# JL7016M8.net
KiCad netlist of a schematic drawn in Altium Designer
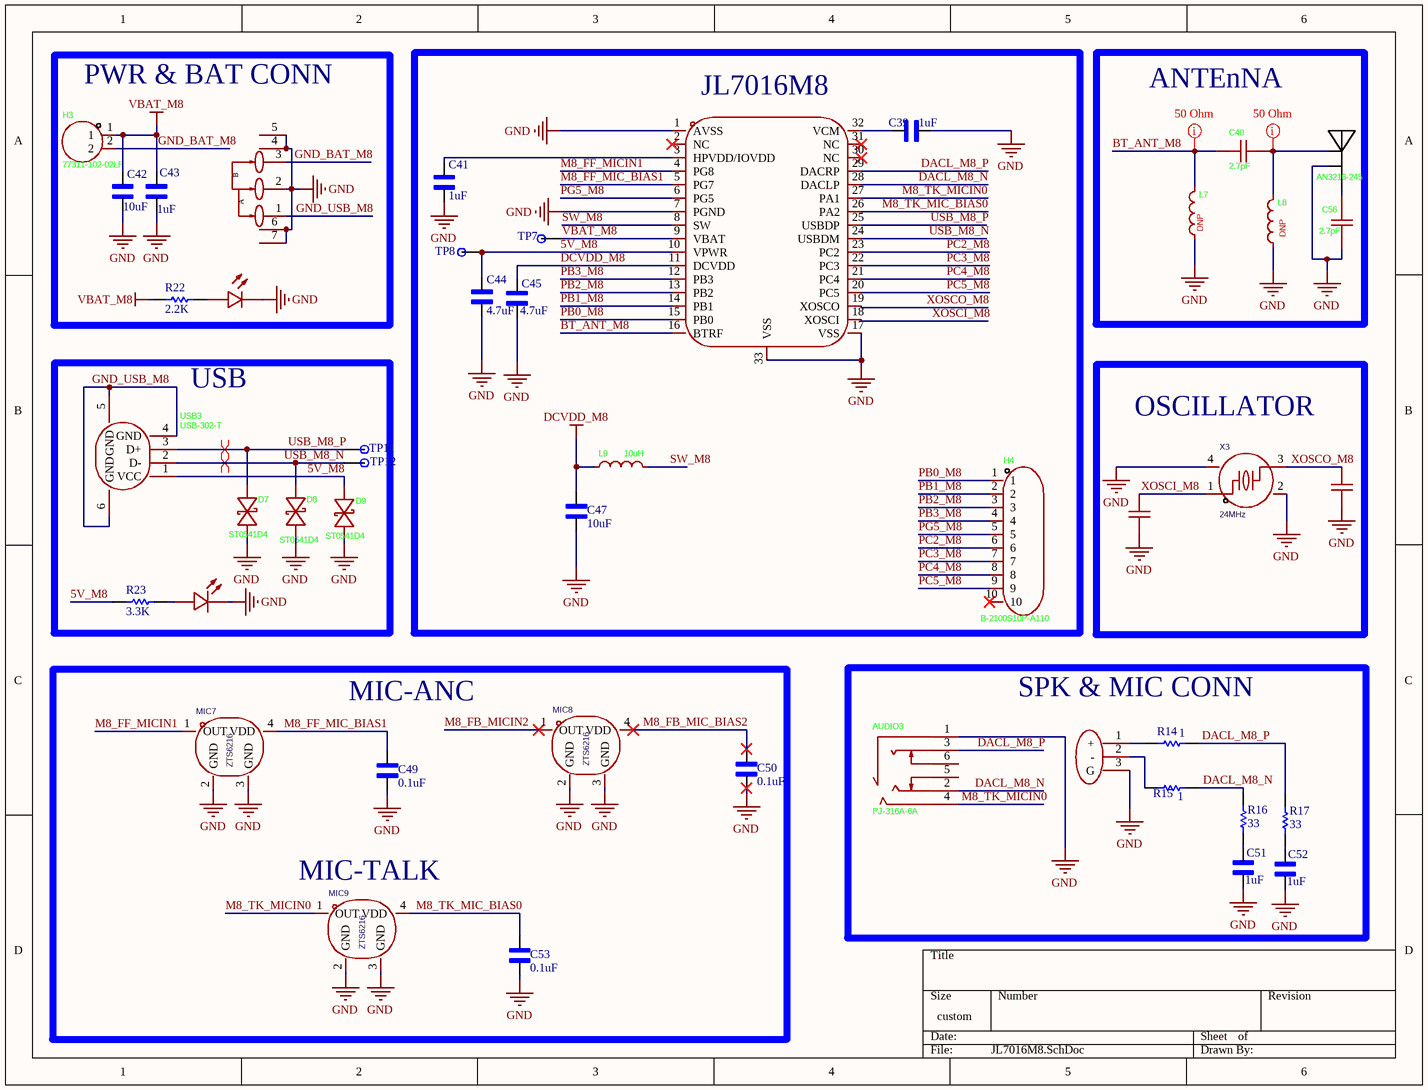
[diagram p0: JL7016M8.SchDoc]

(export (version "E")
  (design (tool "Eeschema 10.0.6"))
  (components
    (comp (ref "ANT3")
      (value "AN3216-245")
      (footprint "CUSTOME ANTEENA")
      (fields (field (name "MANUFACTURER") "Rainsun(霖昱微)") (field (name "POWER") "1W"))
      (libsource (lib "JEILI_DEV_BOARD") (part "AN3216-245"))
    )
    (comp (ref "AUDIO3")
      (value "PJ-316A-6A")
      (footprint "AUDIO-SMD_PJ-316A-6A")
      (fields (field (name "MANUFACTURER") "韩国韩荣"))
      (libsource (lib "JEILI_DEV_BOARD") (part "PJ-316A-6A"))
    )
    (comp (ref "C39") (value "1uF") (footprint "CAPC3216X170N") (libsource (lib "") (part "CAP_1uF_2")))
    (comp (ref "C40")
      (value "2.7pF")
      (footprint "C0603")
      (fields (field (name "MANUFACTURER") "FH(风华)") (field (name "MANUFACTURER PART") "0603CG2R7C500NT"))
      (libsource (lib "JEILI_DEV_BOARD") (part "0603CG2R7C500NT"))
    )
    (comp (ref "C41")
      (value "1uF")
      (footprint "CAPC3216X170N")
      (libsource (lib "JEILI_DEV_BOARD") (part "CAP_1uF"))
    )
    (comp (ref "C42")
      (value "10uF")
      (footprint "CAPC3216X170N")
      (libsource (lib "JEILI_DEV_BOARD") (part "CAP_10F"))
    )
    (comp (ref "C43")
      (value "1uF")
      (footprint "CAPC3216X170N")
      (libsource (lib "JEILI_DEV_BOARD") (part "CAP_1uF"))
    )
    (comp (ref "C44")
      (value "4.7uF")
      (footprint "CAPC3216X170N")
      (fields (field (name "Comment") "1uF"))
      (libsource (lib "JEILI_DEV_BOARD") (part "CAP_1uF"))
    )
    (comp (ref "C45")
      (value "4.7uF")
      (footprint "CAPC3216X170N")
      (fields (field (name "Comment") "1uF"))
      (libsource (lib "JEILI_DEV_BOARD") (part "CAP_1uF"))
    )
    (comp (ref "C46")
      (value "12pF")
      (footprint "CAPC3216X170N")
      (fields
        (field (name "MANUFACTURER") "FH(风华)")
        (field (name "MANUFACTURER PART") "0402CG120J500NT")
        (field (name "TOLERANCE") "±5%")
      )
      (libsource (lib "JEILI_DEV_BOARD") (part "0402CG120J500NT"))
    )
    (comp (ref "C47")
      (value "10uF")
      (footprint "CAPC3216X170N")
      (libsource (lib "JEILI_DEV_BOARD") (part "CAP_10F"))
    )
    (comp (ref "C48")
      (value "12pF")
      (footprint "CAPC3216X170N")
      (fields
        (field (name "MANUFACTURER") "FH(风华)")
        (field (name "MANUFACTURER PART") "0402CG120J500NT")
        (field (name "TOLERANCE") "±5%")
      )
      (libsource (lib "JEILI_DEV_BOARD") (part "0402CG120J500NT"))
    )
    (comp (ref "C49")
      (value "0.1uF")
      (footprint "CAPC3216X170N")
      (description "100nF 10V X7R ±5% 0402 Multilayer Ceramic Capacitors MLCC - SMD/SMT ROHS")
      (fields (field (name "MANUFACTURER") "Walsin Tech Corp") (field (name "MFR.PART #") "0402B104J100CT"))
      (libsource (lib "Glasses_EEG_V2.0") (part "CAP_0.1uF"))
    )
    (comp (ref "C50")
      (value "0.1uF")
      (footprint "CAPC3216X170N")
      (description "100nF 10V X7R ±5% 0402 Multilayer Ceramic Capacitors MLCC - SMD/SMT ROHS")
      (fields (field (name "MANUFACTURER") "Walsin Tech Corp") (field (name "MFR.PART #") "0402B104J100CT"))
      (libsource (lib "Glasses_EEG_V2.0") (part "CAP_0.1uF"))
    )
    (comp (ref "C51") (value "1uF") (footprint "CAPC3216X170N") (libsource (lib "") (part "CAP_1uF_1")))
    (comp (ref "C52") (value "1uF") (footprint "CAPC3216X170N") (libsource (lib "") (part "CAP_1uF_1")))
    (comp (ref "C53")
      (value "0.1uF")
      (footprint "CAPC3216X170N")
      (description "100nF 10V X7R ±5% 0402 Multilayer Ceramic Capacitors MLCC - SMD/SMT ROHS")
      (fields (field (name "MANUFACTURER") "Walsin Tech Corp") (field (name "MFR.PART #") "0402B104J100CT"))
      (libsource (lib "Glasses_EEG_V2.0") (part "CAP_0.1uF"))
    )
    (comp (ref "C56")
      (value "2.7pF")
      (footprint "C0402")
      (fields (field (name "MANUFACTURER") "FH(风华)") (field (name "MANUFACTURER PART") "0603CG2R7C500NT"))
      (libsource (lib "JEILI_DEV_BOARD") (part "0603CG2R7C500NT"))
    )
    (comp (ref "D7")
      (value "ST0541D4")
      (footprint "DFN1006-BI")
      (fields (field (name "MANUFACTURER") "Leiditech(雷卯电子)"))
      (libsource (lib "JEILI_DEV_BOARD") (part "ST0541D4"))
    )
    (comp (ref "D8")
      (value "ST0541D4")
      (footprint "DFN1006-BI")
      (fields (field (name "MANUFACTURER") "Leiditech(雷卯电子)"))
      (libsource (lib "JEILI_DEV_BOARD") (part "ST0541D4"))
    )
    (comp (ref "D9")
      (value "ST0541D4")
      (footprint "DFN1006-BI")
      (fields (field (name "MANUFACTURER") "Leiditech(雷卯电子)"))
      (libsource (lib "JEILI_DEV_BOARD") (part "ST0541D4"))
    )
    (comp (ref "H3")
      (value "77311-102-02LF")
      (footprint "HDR-TH_2P-P2.54-V-M-1")
      (fields (field (name "MANUFACTURER") "Amphenol"))
      (libsource (lib "JEILI_DEV_BOARD") (part "77311-102-02LF"))
    )
    (comp (ref "H4")
      (value "B-2100S10P-A110")
      (footprint "HDR-TH_10P-P2.54-V-M-1")
      (fields (field (name "MANUFACTURER") "Ckmtw(灿科盟)"))
      (libsource (lib "JEILI_DEV_BOARD") (part "B-2100S10P-A110"))
    )
    (comp (ref "L7")
      (value "DNP")
      (footprint "L0603")
      (fields
        (field (name "MANUFACTURER") "muRata(村田)")
        (field (name "MANUFACTURER PART") "DFE18SAN1R0ME0L")
        (field (name "TOLERANCE") "±20%")
      )
      (libsource (lib "JEILI_DEV_BOARD") (part "33nH"))
    )
    (comp (ref "L8")
      (value "DNP")
      (footprint "L0603")
      (fields
        (field (name "MANUFACTURER") "muRata(村田)")
        (field (name "MANUFACTURER PART") "DFE18SAN1R0ME0L")
        (field (name "TOLERANCE") "±20%")
      )
      (libsource (lib "JEILI_DEV_BOARD") (part "33nH"))
    )
    (comp (ref "L9") (value "10uH") (footprint "L0603") (libsource (lib "JEILI_DEV_BOARD") (part "10uH")))
    (comp (ref "LED5")
      (value "LTST-C191GKT")
      (footprint "LED0603-R-RD_GREEN")
      (fields (field (name "MANUFACTURER") "LITEON(光宝)"))
      (libsource (lib "JEILI_DEV_BOARD") (part "LTST-C191GKT"))
    )
    (comp (ref "LED6")
      (value "KT-0603R")
      (footprint "LED0603-RD")
      (fields (field (name "MANUFACTURER") "KENTO"))
      (libsource (lib "JEILI_DEV_BOARD") (part "KT-0603R"))
    )
    (comp (ref "MIC7")
      (value "ZTS6216")
      (footprint "MIC-SMD_4P-L2.8-W1.9-P1.84-TL")
      (fields (field (name "MANUFACTURER") "ZILLTEK(钰太)"))
      (libsource (lib "Glasses_EEG_V2.0") (part "ZTS6216"))
    )
    (comp (ref "MIC8")
      (value "ZTS6216")
      (footprint "MIC-SMD_4P-L2.8-W1.9-P1.84-TL")
      (fields (field (name "MANUFACTURER") "ZILLTEK(钰太)"))
      (libsource (lib "Glasses_EEG_V2.0") (part "ZTS6216"))
    )
    (comp (ref "MIC9")
      (value "ZTS6216")
      (footprint "MIC-SMD_4P-L2.8-W1.9-P1.84-TL")
      (fields (field (name "MANUFACTURER") "ZILLTEK(钰太)"))
      (libsource (lib "Glasses_EEG_V2.0") (part "ZTS6216"))
    )
    (comp (ref "P4")
      (value "1.27-1*3P针")
      (footprint "HDR-TH_3P-P1.27-V-M-1")
      (fields (field (name "MANUFACTURER") "BOOMELE(博穆精密)"))
      (libsource (lib "JEILI_DEV_BOARD") (part "1.27-1*3P针"))
    )
    (comp (ref "R14")
      (value "1")
      (footprint "R0603")
      (fields
        (field (name "MANUFACTURER") "YAGEO")
        (field (name "MFR.PART #") "RC0402JR-0733RL")
        (field (name "JLCPCB PART #") "C137880")
      )
      (libsource (lib "JEILI_DEV_BOARD") (part "RES_1"))
    )
    (comp (ref "R15")
      (value "1")
      (footprint "R0603")
      (fields
        (field (name "MANUFACTURER") "YAGEO")
        (field (name "MFR.PART #") "RC0402JR-0733RL")
        (field (name "JLCPCB PART #") "C137880")
      )
      (libsource (lib "JEILI_DEV_BOARD") (part "RES_1"))
    )
    (comp (ref "R16")
      (value "33")
      (footprint "R0603")
      (fields
        (field (name "MANUFACTURER") "YAGEO")
        (field (name "MFR.PART #") "RC0402JR-0733RL")
        (field (name "JLCPCB PART #") "C137880")
      )
      (libsource (lib "JEILI_DEV_BOARD") (part "RES_33"))
    )
    (comp (ref "R17")
      (value "33")
      (footprint "R0603")
      (fields
        (field (name "MANUFACTURER") "YAGEO")
        (field (name "MFR.PART #") "RC0402JR-0733RL")
        (field (name "JLCPCB PART #") "C137880")
      )
      (libsource (lib "JEILI_DEV_BOARD") (part "RES_33"))
    )
    (comp (ref "R22")
      (value "2.2K")
      (footprint "R1206")
      (fields
        (field (name "MANUFACTURER") "YAGEO")
        (field (name "MFR.PART #") "RC0402JR-0733RL")
        (field (name "JLCPCB PART #") "C137880")
      )
      (libsource (lib "JEILI_DEV_BOARD") (part "RES_2.2K"))
    )
    (comp (ref "R23")
      (value "3.3K")
      (footprint "R1206")
      (fields
        (field (name "MANUFACTURER") "YAGEO")
        (field (name "MFR.PART #") "RC0402JR-0733RL")
        (field (name "JLCPCB PART #") "C137880")
      )
      (libsource (lib "JEILI_DEV_BOARD") (part "RES_3.3K"))
    )
    (comp (ref "SW3")
      (value "MK-12C02-G015")
      (footprint "SW-SMD_G-SWITCH_MK-12C02-G015")
      (fields (field (name "MANUFACTURER") "G-Switch(品赞)"))
      (libsource (lib "JEILI_DEV_BOARD") (part "MK-12C02-G015_C2911519"))
    )
    (comp (ref "TP7")
      (value "*")
      (footprint "TP")
      (description "test point")
      (libsource (lib "*") (part "TP"))
    )
    (comp (ref "TP8")
      (value "*")
      (footprint "TP")
      (description "test point")
      (libsource (lib "*") (part "TP"))
    )
    (comp (ref "TP11")
      (value "TP")
      (footprint "TP")
      (description "test point")
      (libsource (lib "JEILI_DEV_BOARD") (part "TP"))
    )
    (comp (ref "TP12")
      (value "TP")
      (footprint "TP")
      (description "test point")
      (libsource (lib "JEILI_DEV_BOARD") (part "TP"))
    )
    (comp (ref "U3")
      (value "JL7016M8")
      (footprint "QFN-32_L4.0-W4.0-P0.40-TL-EP2.7_1")
      (fields (field (name "MANUFACTURER") "JL(杰理)"))
      (libsource (lib "JEILI_DEV_BOARD") (part "JL7016M8"))
    )
    (comp (ref "USB3")
      (value "USB-302-T")
      (footprint "USB-A-TH_USB-302-T")
      (fields (field (name "MANUFACTURER") "SOFNG(硕方)"))
      (libsource (lib "JEILI_DEV_BOARD") (part "USB-302-T"))
    )
    (comp (ref "X3")
      (value "24MHz")
      (footprint "CRYSTAL-SMD_4P-L2.0-W1.6-BL-A")
      (fields
        (field (name "MANUFACTURER") "YXC(扬兴晶振)")
        (field (name "MANUFACTURER PART") "XL7EL89CKI-111YLC-24M")
      )
      (libsource (lib "Glasses_EEG_V2.0") (part "XL7EL89CKI-111YLC-24M"))
    )
  )
  (nets
    (net (code "1") (name "/5V_M8") (class "Default")
      (node (ref "C44") (pin "1") (pinfunction "1_1") (pintype "passive"))
      (node (ref "D9") (pin "2") (pinfunction "2_2") (pintype "passive"))
      (node (ref "R23") (pin "2") (pinfunction "2_2") (pintype "passive"))
      (node (ref "TP8") (pin "1") (pinfunction "1_1") (pintype "passive"))
      (node (ref "U3") (pin "10") (pinfunction "VPWR_10") (pintype "passive"))
      (node (ref "USB3") (pin "1") (pinfunction "VCC_1") (pintype "passive"))
    )
    (net (code "2") (name "/BT_ANT_M8") (class "Default")
      (node (ref "C40") (pin "1") (pinfunction "1_1") (pintype "passive"))
      (node (ref "L7") (pin "2") (pinfunction "2_2") (pintype "passive"))
      (node (ref "U3") (pin "16") (pinfunction "BTRF_16") (pintype "passive"))
    )
    (net (code "3") (name "/DACL_M8_N") (class "Default")
      (node (ref "AUDIO3") (pin "2") (pinfunction "2_2") (pintype "passive"))
      (node (ref "R15") (pin "1") (pinfunction "1_1") (pintype "passive"))
      (node (ref "R16") (pin "1") (pinfunction "1_1") (pintype "passive"))
      (node (ref "U3") (pin "28") (pinfunction "DACLP_28") (pintype "passive"))
    )
    (net (code "4") (name "/DACL_M8_P") (class "Default")
      (node (ref "AUDIO3") (pin "3") (pinfunction "3_3") (pintype "passive"))
      (node (ref "R14") (pin "1") (pinfunction "1_1") (pintype "passive"))
      (node (ref "R17") (pin "1") (pinfunction "1_1") (pintype "passive"))
      (node (ref "U3") (pin "29") (pinfunction "DACRP_29") (pintype "passive"))
    )
    (net (code "5") (name "/GND_BAT_M8") (class "Default")
      (node (ref "H3") (pin "2") (pinfunction "2_2") (pintype "passive"))
      (node (ref "SW3") (pin "3") (pinfunction "3_3") (pintype "passive"))
    )
    (net (code "6") (name "/GND_USB_M8") (class "Default")
      (node (ref "SW3") (pin "1") (pinfunction "1_1") (pintype "passive"))
      (node (ref "USB3") (pin "4") (pinfunction "GND_4") (pintype "passive"))
      (node (ref "USB3") (pin "5") (pinfunction "GND_5") (pintype "passive"))
      (node (ref "USB3") (pin "6") (pinfunction "GND_6") (pintype "passive"))
    )
    (net (code "7") (name "/M8_FB_MICIN2") (class "Default")
      (node (ref "MIC8") (pin "1") (pinfunction "OUT_1") (pintype "passive+no_connect"))
    )
    (net (code "8") (name "/M8_FB_MIC_BIAS2") (class "Default")
      (node (ref "C50") (pin "2") (pinfunction "2_2") (pintype "passive"))
      (node (ref "MIC8") (pin "4") (pinfunction "VDD_4") (pintype "passive"))
    )
    (net (code "9") (name "/M8_FF_MICIN1") (class "Default")
      (node (ref "MIC7") (pin "1") (pinfunction "OUT_1") (pintype "passive"))
      (node (ref "U3") (pin "4") (pinfunction "PG8_4") (pintype "passive"))
    )
    (net (code "10") (name "/M8_FF_MIC_BIAS1") (class "Default")
      (node (ref "C49") (pin "2") (pinfunction "2_2") (pintype "passive"))
      (node (ref "MIC7") (pin "4") (pinfunction "VDD_4") (pintype "passive"))
      (node (ref "U3") (pin "5") (pinfunction "PG7_5") (pintype "passive"))
    )
    (net (code "11") (name "/M8_TK_MICIN0") (class "Default")
      (node (ref "AUDIO3") (pin "4") (pinfunction "4_4") (pintype "passive"))
      (node (ref "MIC9") (pin "1") (pinfunction "OUT_1") (pintype "passive"))
      (node (ref "U3") (pin "27") (pinfunction "PA1_27") (pintype "passive"))
    )
    (net (code "12") (name "/M8_TK_MIC_BIAS0") (class "Default")
      (node (ref "C53") (pin "2") (pinfunction "2_2") (pintype "passive"))
      (node (ref "MIC9") (pin "4") (pinfunction "VDD_4") (pintype "passive"))
      (node (ref "U3") (pin "26") (pinfunction "PA2_26") (pintype "passive"))
    )
    (net (code "13") (name "/PB0_M8") (class "Default")
      (node (ref "H4") (pin "1") (pinfunction "1_1") (pintype "passive"))
      (node (ref "U3") (pin "15") (pinfunction "PB0_15") (pintype "passive"))
    )
    (net (code "14") (name "/PB1_M8") (class "Default")
      (node (ref "H4") (pin "2") (pinfunction "2_2") (pintype "passive"))
      (node (ref "U3") (pin "14") (pinfunction "PB1_14") (pintype "passive"))
    )
    (net (code "15") (name "/PB2_M8") (class "Default")
      (node (ref "H4") (pin "3") (pinfunction "3_3") (pintype "passive"))
      (node (ref "U3") (pin "13") (pinfunction "PB2_13") (pintype "passive"))
    )
    (net (code "16") (name "/PB3_M8") (class "Default")
      (node (ref "H4") (pin "4") (pinfunction "4_4") (pintype "passive"))
      (node (ref "U3") (pin "12") (pinfunction "PB3_12") (pintype "passive"))
    )
    (net (code "17") (name "/PC2_M8") (class "Default")
      (node (ref "H4") (pin "6") (pinfunction "6_6") (pintype "passive"))
      (node (ref "U3") (pin "23") (pinfunction "PC2_23") (pintype "passive"))
    )
    (net (code "18") (name "/PC3_M8") (class "Default")
      (node (ref "H4") (pin "7") (pinfunction "7_7") (pintype "passive"))
      (node (ref "U3") (pin "22") (pinfunction "PC3_22") (pintype "passive"))
    )
    (net (code "19") (name "/PC4_M8") (class "Default")
      (node (ref "H4") (pin "8") (pinfunction "8_8") (pintype "passive"))
      (node (ref "U3") (pin "21") (pinfunction "PC4_21") (pintype "passive"))
    )
    (net (code "20") (name "/PC5_M8") (class "Default")
      (node (ref "H4") (pin "9") (pinfunction "9_9") (pintype "passive"))
      (node (ref "U3") (pin "20") (pinfunction "PC5_20") (pintype "passive"))
    )
    (net (code "21") (name "/PG5_M8") (class "Default")
      (node (ref "H4") (pin "5") (pinfunction "5_5") (pintype "passive"))
      (node (ref "U3") (pin "6") (pinfunction "PG5_6") (pintype "passive"))
    )
    (net (code "22") (name "/SW_M8") (class "Default")
      (node (ref "L9") (pin "2") (pinfunction "2_2") (pintype "passive"))
      (node (ref "U3") (pin "8") (pinfunction "SW_8") (pintype "passive"))
    )
    (net (code "23") (name "/USB_M8_N") (class "Default")
      (node (ref "D8") (pin "2") (pinfunction "2_2") (pintype "passive"))
      (node (ref "TP12") (pin "1") (pinfunction "1_1") (pintype "passive"))
      (node (ref "U3") (pin "24") (pinfunction "USBDM_24") (pintype "passive"))
      (node (ref "USB3") (pin "2") (pinfunction "D-_2") (pintype "passive"))
    )
    (net (code "24") (name "/USB_M8_P") (class "Default")
      (node (ref "D7") (pin "2") (pinfunction "2_2") (pintype "passive"))
      (node (ref "TP11") (pin "1") (pinfunction "1_1") (pintype "passive"))
      (node (ref "U3") (pin "25") (pinfunction "USBDP_25") (pintype "passive"))
      (node (ref "USB3") (pin "3") (pinfunction "D+_3") (pintype "passive"))
    )
    (net (code "25") (name "/XOSCI_M8") (class "Default")
      (node (ref "C48") (pin "2") (pinfunction "2_2") (pintype "passive"))
      (node (ref "U3") (pin "18") (pinfunction "XOSCI_18") (pintype "passive"))
      (node (ref "X3") (pin "1") (pinfunction "1_1") (pintype "passive"))
    )
    (net (code "26") (name "/XOSCO_M8") (class "Default")
      (node (ref "C46") (pin "2") (pinfunction "2_2") (pintype "passive"))
      (node (ref "U3") (pin "19") (pinfunction "XOSCO_19") (pintype "passive"))
      (node (ref "X3") (pin "3") (pinfunction "3_3") (pintype "passive"))
    )
    (net (code "27") (name "DCVDD_M8") (class "Default")
      (node (ref "C45") (pin "1") (pinfunction "1_1") (pintype "passive"))
      (node (ref "C47") (pin "2") (pinfunction "2_2") (pintype "passive"))
      (node (ref "L9") (pin "1") (pinfunction "1_1") (pintype "passive"))
      (node (ref "U3") (pin "11") (pinfunction "DCVDD_11") (pintype "passive"))
    )
    (net (code "28") (name "GND") (class "Default")
      (node (ref "ANT3") (pin "2") (pinfunction "2_2") (pintype "passive"))
      (node (ref "AUDIO3") (pin "1") (pinfunction "1_1") (pintype "passive"))
      (node (ref "C39") (pin "2") (pinfunction "2_2") (pintype "passive"))
      (node (ref "C41") (pin "2") (pinfunction "2_2") (pintype "passive"))
      (node (ref "C42") (pin "1") (pinfunction "1_1") (pintype "passive"))
      (node (ref "C43") (pin "2") (pinfunction "2_2") (pintype "passive"))
      (node (ref "C44") (pin "2") (pinfunction "2_2") (pintype "passive"))
      (node (ref "C45") (pin "2") (pinfunction "2_2") (pintype "passive"))
      (node (ref "C46") (pin "1") (pinfunction "1_1") (pintype "passive"))
      (node (ref "C47") (pin "1") (pinfunction "1_1") (pintype "passive"))
      (node (ref "C48") (pin "1") (pinfunction "1_1") (pintype "passive"))
      (node (ref "C49") (pin "1") (pinfunction "1_1") (pintype "passive"))
      (node (ref "C50") (pin "1") (pinfunction "1_1") (pintype "passive"))
      (node (ref "C51") (pin "1") (pinfunction "1_1") (pintype "passive"))
      (node (ref "C52") (pin "1") (pinfunction "1_1") (pintype "passive"))
      (node (ref "C53") (pin "1") (pinfunction "1_1") (pintype "passive"))
      (node (ref "C56") (pin "1") (pinfunction "1_1") (pintype "passive"))
      (node (ref "D7") (pin "1") (pinfunction "1_1") (pintype "passive"))
      (node (ref "D8") (pin "1") (pinfunction "1_1") (pintype "passive"))
      (node (ref "D9") (pin "1") (pinfunction "1_1") (pintype "passive"))
      (node (ref "L7") (pin "1") (pinfunction "1_1") (pintype "passive"))
      (node (ref "L8") (pin "1") (pinfunction "1_1") (pintype "passive"))
      (node (ref "LED5") (pin "2") (pinfunction "C_2") (pintype "passive"))
      (node (ref "LED6") (pin "1") (pinfunction "K_1") (pintype "passive"))
      (node (ref "MIC7") (pin "2") (pinfunction "GND_2") (pintype "passive"))
      (node (ref "MIC7") (pin "3") (pinfunction "GND_3") (pintype "passive"))
      (node (ref "MIC8") (pin "2") (pinfunction "GND_2") (pintype "passive"))
      (node (ref "MIC8") (pin "3") (pinfunction "GND_3") (pintype "passive"))
      (node (ref "MIC9") (pin "2") (pinfunction "GND_2") (pintype "passive"))
      (node (ref "MIC9") (pin "3") (pinfunction "GND_3") (pintype "passive"))
      (node (ref "P4") (pin "3") (pinfunction "G_3") (pintype "passive"))
      (node (ref "SW3") (pin "2") (pinfunction "2_2") (pintype "passive"))
      (node (ref "SW3") (pin "4") (pinfunction "4_4") (pintype "passive"))
      (node (ref "SW3") (pin "5") (pinfunction "5_5") (pintype "passive"))
      (node (ref "SW3") (pin "6") (pinfunction "6_6") (pintype "passive"))
      (node (ref "SW3") (pin "7") (pinfunction "7_7") (pintype "passive"))
      (node (ref "U3") (pin "1") (pinfunction "AVSS_1") (pintype "passive"))
      (node (ref "U3") (pin "17") (pinfunction "VSS_17") (pintype "passive"))
      (node (ref "U3") (pin "33") (pinfunction "VSS_33") (pintype "passive"))
      (node (ref "U3") (pin "7") (pinfunction "PGND_7") (pintype "passive"))
      (node (ref "X3") (pin "2") (pinfunction "GND_2") (pintype "passive"))
      (node (ref "X3") (pin "4") (pinfunction "GND_4") (pintype "passive"))
    )
    (net (code "29") (name "Net-(ANT3-Pad1)") (class "Default")
      (node (ref "ANT3") (pin "1") (pinfunction "1_1") (pintype "passive"))
      (node (ref "C40") (pin "2") (pinfunction "2_2") (pintype "passive"))
      (node (ref "L8") (pin "2") (pinfunction "2_2") (pintype "passive"))
    )
    (net (code "30") (name "Net-(ANT3-Pad3)") (class "Default")
      (node (ref "ANT3") (pin "3") (pinfunction "3_3") (pintype "passive"))
      (node (ref "C56") (pin "2") (pinfunction "2_2") (pintype "passive"))
    )
    (net (code "31") (name "Net-(C51-Pad2)") (class "Default")
      (node (ref "C51") (pin "2") (pinfunction "2_2") (pintype "passive"))
      (node (ref "R16") (pin "2") (pinfunction "2_2") (pintype "passive"))
    )
    (net (code "32") (name "Net-(C52-Pad2)") (class "Default")
      (node (ref "C52") (pin "2") (pinfunction "2_2") (pintype "passive"))
      (node (ref "R17") (pin "2") (pinfunction "2_2") (pintype "passive"))
    )
    (net (code "33") (name "Net-(LED5-A)") (class "Default")
      (node (ref "LED5") (pin "1") (pinfunction "A_1") (pintype "passive"))
      (node (ref "R22") (pin "1") (pinfunction "1_1") (pintype "passive"))
    )
    (net (code "34") (name "Net-(LED6-A)") (class "Default")
      (node (ref "LED6") (pin "2") (pinfunction "A_2") (pintype "passive"))
      (node (ref "R23") (pin "1") (pinfunction "1_1") (pintype "passive"))
    )
    (net (code "35") (name "Net-(P4-+)") (class "Default")
      (node (ref "P4") (pin "1") (pinfunction "+_1") (pintype "passive"))
      (node (ref "R14") (pin "2") (pinfunction "2_2") (pintype "passive"))
    )
    (net (code "36") (name "Net-(P4--)") (class "Default")
      (node (ref "P4") (pin "2") (pinfunction "-_2") (pintype "passive"))
      (node (ref "R15") (pin "2") (pinfunction "2_2") (pintype "passive"))
    )
    (net (code "37") (name "Net-(U3-HPVDD{slash}IOVDD)") (class "Default")
      (node (ref "C41") (pin "1") (pinfunction "1_1") (pintype "passive"))
      (node (ref "U3") (pin "3") (pinfunction "HPVDD/IOVDD_3") (pintype "passive"))
    )
    (net (code "38") (name "Net-(U3-VCM)") (class "Default")
      (node (ref "C39") (pin "1") (pinfunction "1_1") (pintype "passive"))
      (node (ref "U3") (pin "32") (pinfunction "VCM_32") (pintype "passive"))
    )
    (net (code "39") (name "VBAT_M8") (class "Default")
      (node (ref "C42") (pin "2") (pinfunction "2_2") (pintype "passive"))
      (node (ref "C43") (pin "1") (pinfunction "1_1") (pintype "passive"))
      (node (ref "H3") (pin "1") (pinfunction "1_1") (pintype "passive"))
      (node (ref "R22") (pin "2") (pinfunction "2_2") (pintype "passive"))
      (node (ref "TP7") (pin "1") (pinfunction "1_1") (pintype "passive"))
      (node (ref "U3") (pin "9") (pinfunction "VBAT_9") (pintype "passive"))
    )
    (net (code "40") (name "unconnected-(AUDIO3-Pad5)") (class "Default")
      (node (ref "AUDIO3") (pin "5") (pinfunction "5_5") (pintype "passive"))
    )
    (net (code "41") (name "unconnected-(AUDIO3-Pad6)") (class "Default")
      (node (ref "AUDIO3") (pin "6") (pinfunction "6_6") (pintype "passive"))
    )
    (net (code "42") (name "unconnected-(H4-Pad10)") (class "Default")
      (node (ref "H4") (pin "10") (pinfunction "10_10") (pintype "passive+no_connect"))
    )
    (net (code "43") (name "unconnected-(U3-NC-Pad2)") (class "Default")
      (node (ref "U3") (pin "2") (pinfunction "NC_2") (pintype "passive+no_connect"))
    )
    (net (code "44") (name "unconnected-(U3-NC-Pad30)") (class "Default")
      (node (ref "U3") (pin "30") (pinfunction "NC_30") (pintype "passive+no_connect"))
    )
    (net (code "45") (name "unconnected-(U3-NC-Pad31)") (class "Default")
      (node (ref "U3") (pin "31") (pinfunction "NC_31") (pintype "passive+no_connect"))
    )
  )
)
